# STM32H750VBT6_USB3300.net
KiCad netlist of a schematic drawn in EasyEDA Pro
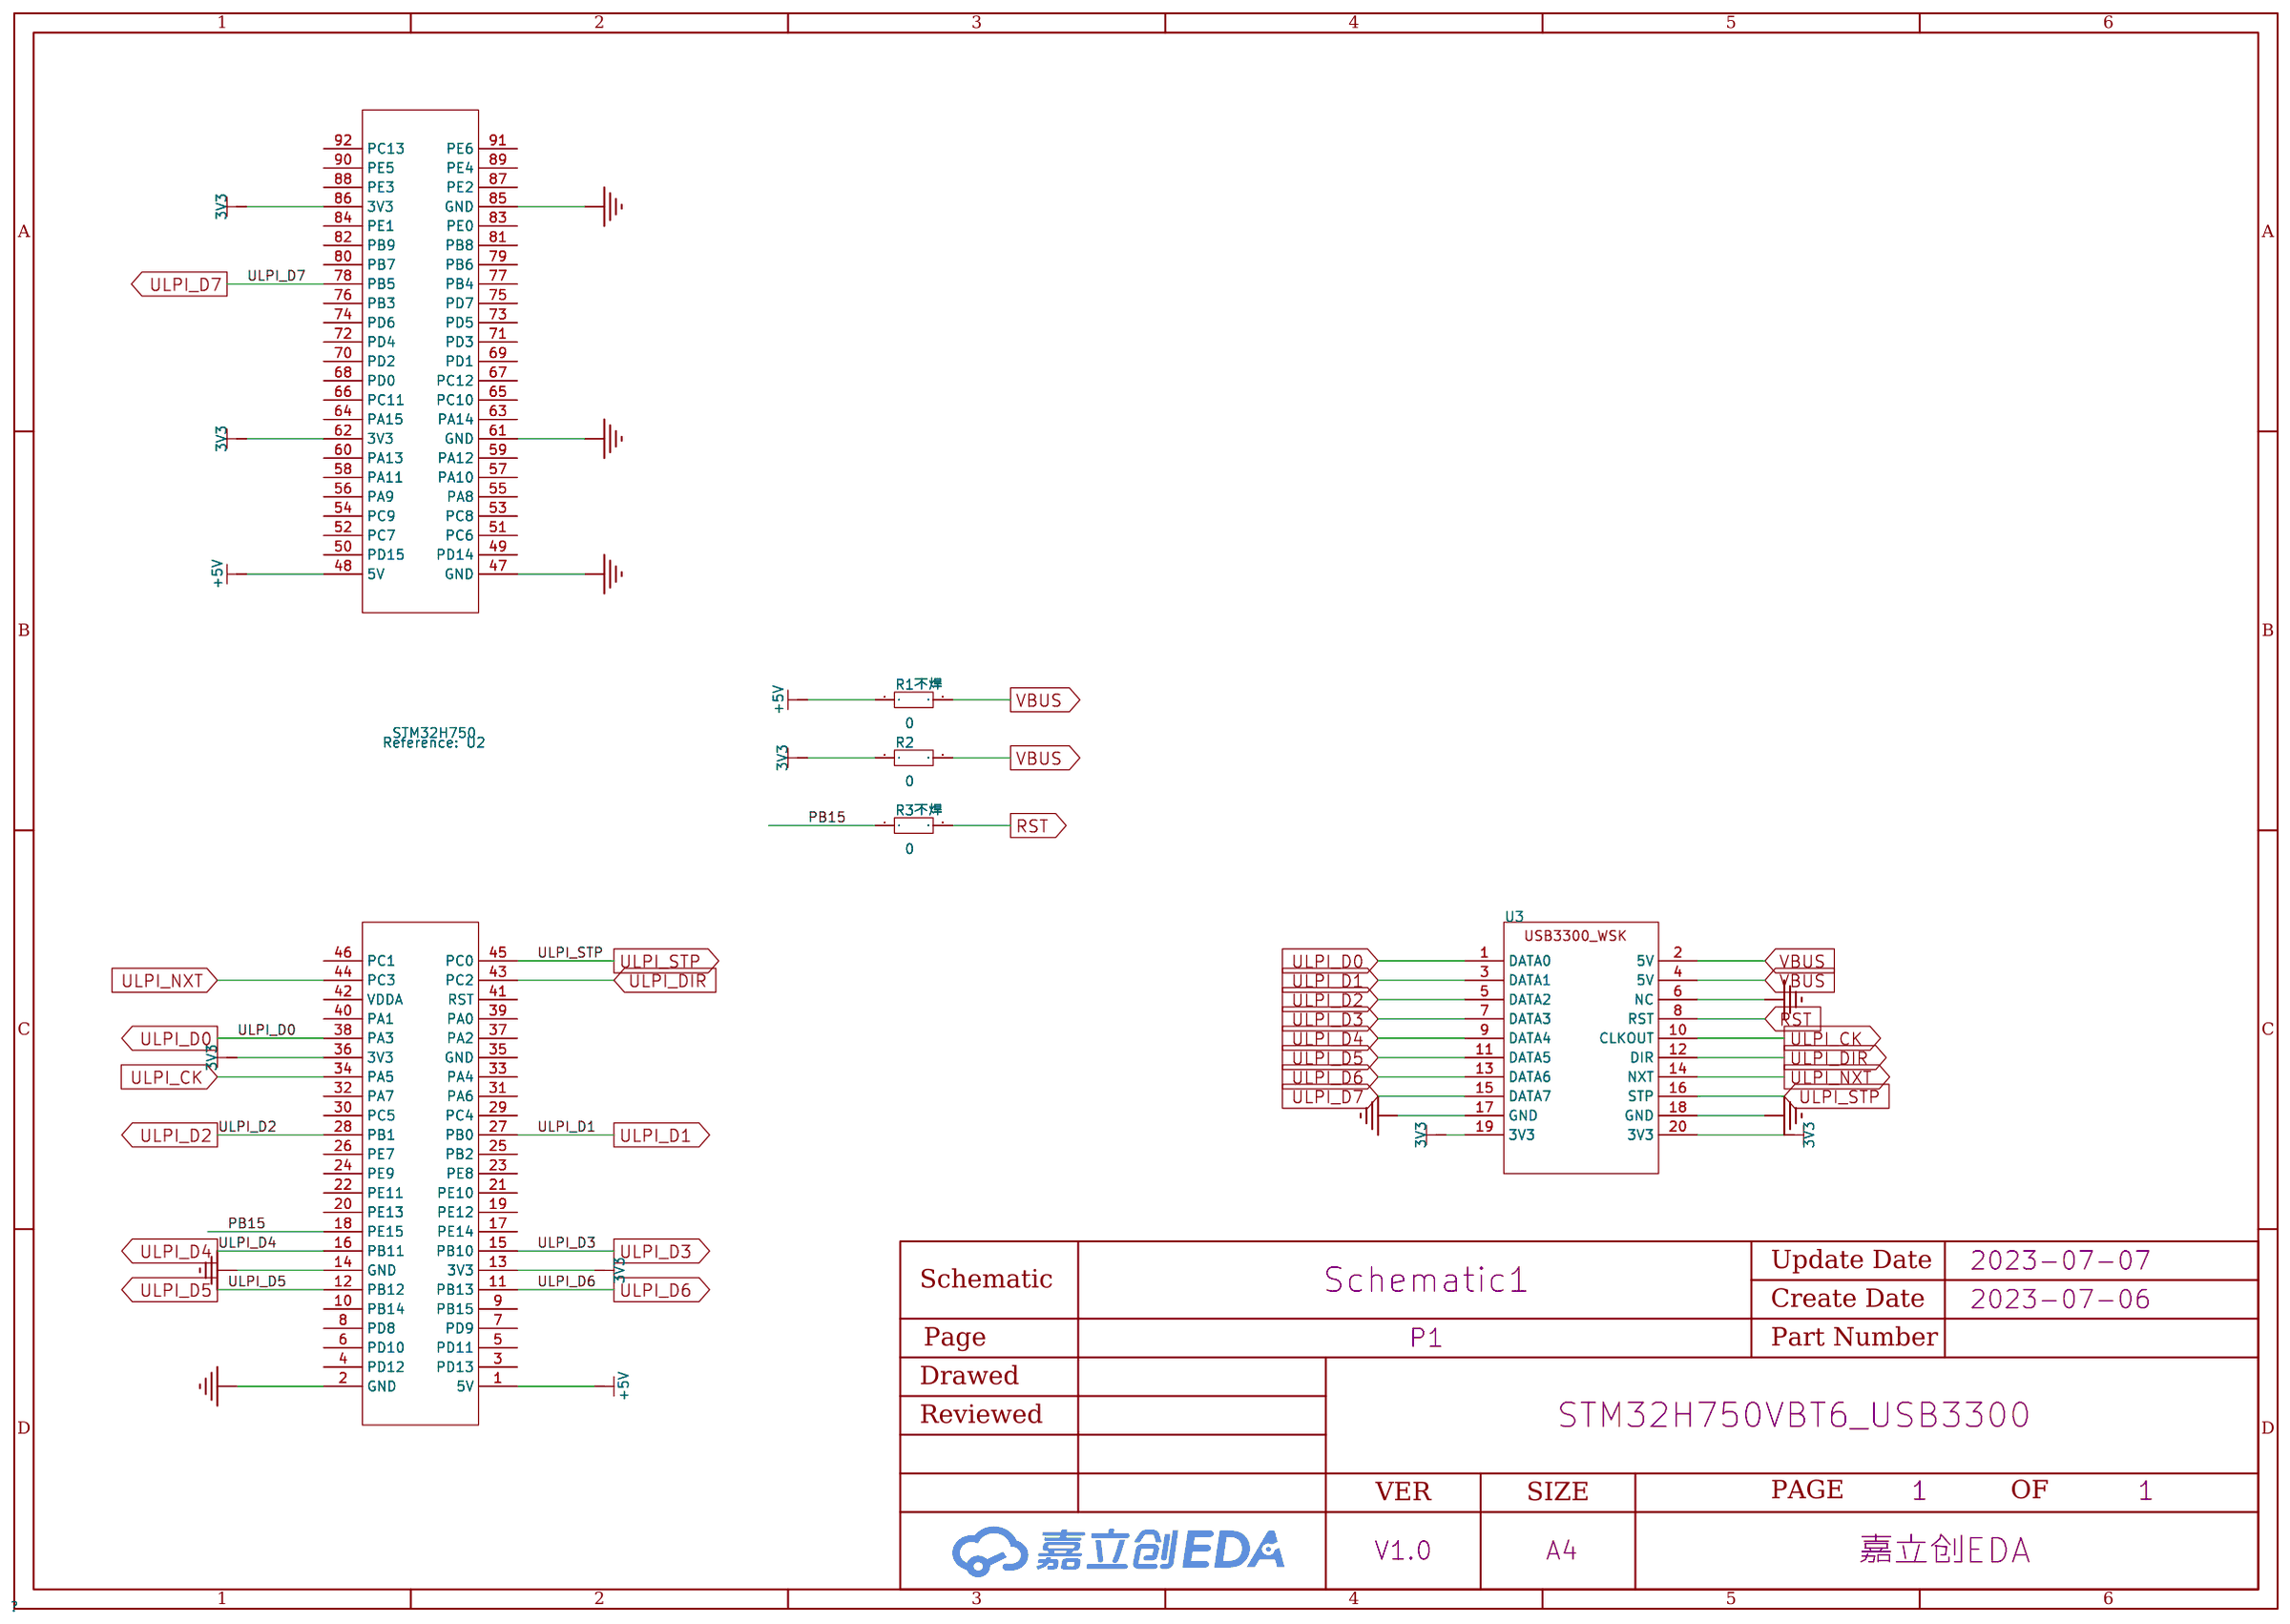
[diagram p0: schematic sheet]

(export (version "E")
  (design (tool "Eeschema 10.0.6"))
  (components
    (comp (ref "R1不焊") (value "0") (footprint "easyedapro:R0603") (libsource (lib "easyedapro") (part "电阻")))
    (comp (ref "R2") (value "0") (footprint "easyedapro:R0603") (libsource (lib "easyedapro") (part "电阻")))
    (comp (ref "R3不焊") (value "0") (footprint "easyedapro:R0603") (libsource (lib "easyedapro") (part "电阻")))
    (comp (ref "U2")
      (value "STM32H750")
      (description "STM32H750VBT6核心板")
      (libsource (lib "easyedapro") (part "STM32H750VBT6"))
    )
    (comp (ref "U3")
      (value "~")
      (description "微雪USB3300 ULPI接口模块")
      (libsource (lib "easyedapro") (part "USB3300_wireshark"))
    )
  )
  (nets
    (net (code "1") (name "+5V") (class "Default")
      (node (ref "R1不焊") (pin "1") (pinfunction "1_1") (pintype "input"))
      (node (ref "U2") (pin "1") (pinfunction "5V_1") (pintype "input"))
      (node (ref "U2") (pin "48") (pinfunction "5V_48") (pintype "input"))
    )
    (net (code "2") (name "/PB15") (class "Default")
      (node (ref "R3不焊") (pin "1") (pinfunction "1_1") (pintype "input"))
      (node (ref "U2") (pin "18") (pinfunction "PE15_18") (pintype "input"))
    )
    (net (code "3") (name "3V3") (class "Default")
      (node (ref "R2") (pin "1") (pinfunction "1_1") (pintype "input"))
      (node (ref "U2") (pin "13") (pinfunction "3V3_13") (pintype "input"))
      (node (ref "U2") (pin "36") (pinfunction "3V3_36") (pintype "input"))
      (node (ref "U2") (pin "62") (pinfunction "3V3_62") (pintype "input"))
      (node (ref "U2") (pin "86") (pinfunction "3V3_86") (pintype "input"))
      (node (ref "U3") (pin "19") (pinfunction "3V3_19") (pintype "input"))
      (node (ref "U3") (pin "20") (pinfunction "3V3_20") (pintype "input"))
    )
    (net (code "4") (name "GND") (class "Default")
      (node (ref "U2") (pin "14") (pinfunction "GND_14") (pintype "input"))
      (node (ref "U2") (pin "2") (pinfunction "GND_2") (pintype "input"))
      (node (ref "U2") (pin "47") (pinfunction "GND_47") (pintype "input"))
      (node (ref "U2") (pin "61") (pinfunction "GND_61") (pintype "input"))
      (node (ref "U2") (pin "85") (pinfunction "GND_85") (pintype "input"))
      (node (ref "U3") (pin "17") (pinfunction "GND_17") (pintype "input"))
      (node (ref "U3") (pin "18") (pinfunction "GND_18") (pintype "input"))
      (node (ref "U3") (pin "6") (pinfunction "NC_6") (pintype "input"))
    )
    (net (code "5") (name "RST") (class "Default")
      (node (ref "R3不焊") (pin "2") (pinfunction "2_2") (pintype "input"))
      (node (ref "U3") (pin "8") (pinfunction "RST_8") (pintype "input"))
    )
    (net (code "6") (name "ULPI_CK") (class "Default")
      (node (ref "U2") (pin "34") (pinfunction "PA5_34") (pintype "input"))
      (node (ref "U3") (pin "10") (pinfunction "CLKOUT_10") (pintype "input"))
    )
    (net (code "7") (name "ULPI_D0") (class "Default")
      (node (ref "U2") (pin "38") (pinfunction "PA3_38") (pintype "input"))
      (node (ref "U3") (pin "1") (pinfunction "DATA0_1") (pintype "input"))
    )
    (net (code "8") (name "ULPI_D1") (class "Default")
      (node (ref "U2") (pin "27") (pinfunction "PB0_27") (pintype "input"))
      (node (ref "U3") (pin "3") (pinfunction "DATA1_3") (pintype "input"))
    )
    (net (code "9") (name "ULPI_D2") (class "Default")
      (node (ref "U2") (pin "28") (pinfunction "PB1_28") (pintype "input"))
      (node (ref "U3") (pin "5") (pinfunction "DATA2_5") (pintype "input"))
    )
    (net (code "10") (name "ULPI_D3") (class "Default")
      (node (ref "U2") (pin "15") (pinfunction "PB10_15") (pintype "input"))
      (node (ref "U3") (pin "7") (pinfunction "DATA3_7") (pintype "input"))
    )
    (net (code "11") (name "ULPI_D4") (class "Default")
      (node (ref "U2") (pin "16") (pinfunction "PB11_16") (pintype "input"))
      (node (ref "U3") (pin "9") (pinfunction "DATA4_9") (pintype "input"))
    )
    (net (code "12") (name "ULPI_D5") (class "Default")
      (node (ref "U2") (pin "12") (pinfunction "PB12_12") (pintype "input"))
      (node (ref "U3") (pin "11") (pinfunction "DATA5_11") (pintype "input"))
    )
    (net (code "13") (name "ULPI_D6") (class "Default")
      (node (ref "U2") (pin "11") (pinfunction "PB13_11") (pintype "input"))
      (node (ref "U3") (pin "13") (pinfunction "DATA6_13") (pintype "input"))
    )
    (net (code "14") (name "ULPI_D7") (class "Default")
      (node (ref "U2") (pin "78") (pinfunction "PB5_78") (pintype "input"))
      (node (ref "U3") (pin "15") (pinfunction "DATA7_15") (pintype "input"))
    )
    (net (code "15") (name "ULPI_DIR") (class "Default")
      (node (ref "U2") (pin "43") (pinfunction "PC2_43") (pintype "input"))
      (node (ref "U3") (pin "12") (pinfunction "DIR_12") (pintype "input"))
    )
    (net (code "16") (name "ULPI_NXT") (class "Default")
      (node (ref "U2") (pin "44") (pinfunction "PC3_44") (pintype "input"))
      (node (ref "U3") (pin "14") (pinfunction "NXT_14") (pintype "input"))
    )
    (net (code "17") (name "ULPI_STP") (class "Default")
      (node (ref "U2") (pin "45") (pinfunction "PC0_45") (pintype "input"))
      (node (ref "U3") (pin "16") (pinfunction "STP_16") (pintype "input"))
    )
    (net (code "18") (name "VBUS") (class "Default")
      (node (ref "R1不焊") (pin "2") (pinfunction "2_2") (pintype "input"))
      (node (ref "R2") (pin "2") (pinfunction "2_2") (pintype "input"))
      (node (ref "U3") (pin "2") (pinfunction "5V_2") (pintype "input"))
      (node (ref "U3") (pin "4") (pinfunction "5V_4") (pintype "input"))
    )
    (net (code "19") (name "unconnected-(U2-GND-Pad35)") (class "Default")
      (node (ref "U2") (pin "35") (pinfunction "GND_35") (pintype "input"))
    )
    (net (code "20") (name "unconnected-(U2-PA0-Pad39)") (class "Default")
      (node (ref "U2") (pin "39") (pinfunction "PA0_39") (pintype "input"))
    )
    (net (code "21") (name "unconnected-(U2-PA1-Pad40)") (class "Default")
      (node (ref "U2") (pin "40") (pinfunction "PA1_40") (pintype "input"))
    )
    (net (code "22") (name "unconnected-(U2-PA2-Pad37)") (class "Default")
      (node (ref "U2") (pin "37") (pinfunction "PA2_37") (pintype "input"))
    )
    (net (code "23") (name "unconnected-(U2-PA4-Pad33)") (class "Default")
      (node (ref "U2") (pin "33") (pinfunction "PA4_33") (pintype "input"))
    )
    (net (code "24") (name "unconnected-(U2-PA6-Pad31)") (class "Default")
      (node (ref "U2") (pin "31") (pinfunction "PA6_31") (pintype "input"))
    )
    (net (code "25") (name "unconnected-(U2-PA7-Pad32)") (class "Default")
      (node (ref "U2") (pin "32") (pinfunction "PA7_32") (pintype "input"))
    )
    (net (code "26") (name "unconnected-(U2-PA8-Pad55)") (class "Default")
      (node (ref "U2") (pin "55") (pinfunction "PA8_55") (pintype "input"))
    )
    (net (code "27") (name "unconnected-(U2-PA9-Pad56)") (class "Default")
      (node (ref "U2") (pin "56") (pinfunction "PA9_56") (pintype "input"))
    )
    (net (code "28") (name "unconnected-(U2-PA10-Pad57)") (class "Default")
      (node (ref "U2") (pin "57") (pinfunction "PA10_57") (pintype "input"))
    )
    (net (code "29") (name "unconnected-(U2-PA11-Pad58)") (class "Default")
      (node (ref "U2") (pin "58") (pinfunction "PA11_58") (pintype "input"))
    )
    (net (code "30") (name "unconnected-(U2-PA12-Pad59)") (class "Default")
      (node (ref "U2") (pin "59") (pinfunction "PA12_59") (pintype "input"))
    )
    (net (code "31") (name "unconnected-(U2-PA13-Pad60)") (class "Default")
      (node (ref "U2") (pin "60") (pinfunction "PA13_60") (pintype "input"))
    )
    (net (code "32") (name "unconnected-(U2-PA14-Pad63)") (class "Default")
      (node (ref "U2") (pin "63") (pinfunction "PA14_63") (pintype "input"))
    )
    (net (code "33") (name "unconnected-(U2-PA15-Pad64)") (class "Default")
      (node (ref "U2") (pin "64") (pinfunction "PA15_64") (pintype "input"))
    )
    (net (code "34") (name "unconnected-(U2-PB2-Pad25)") (class "Default")
      (node (ref "U2") (pin "25") (pinfunction "PB2_25") (pintype "input"))
    )
    (net (code "35") (name "unconnected-(U2-PB3-Pad76)") (class "Default")
      (node (ref "U2") (pin "76") (pinfunction "PB3_76") (pintype "input"))
    )
    (net (code "36") (name "unconnected-(U2-PB4-Pad77)") (class "Default")
      (node (ref "U2") (pin "77") (pinfunction "PB4_77") (pintype "input"))
    )
    (net (code "37") (name "unconnected-(U2-PB6-Pad79)") (class "Default")
      (node (ref "U2") (pin "79") (pinfunction "PB6_79") (pintype "input"))
    )
    (net (code "38") (name "unconnected-(U2-PB7-Pad80)") (class "Default")
      (node (ref "U2") (pin "80") (pinfunction "PB7_80") (pintype "input"))
    )
    (net (code "39") (name "unconnected-(U2-PB8-Pad81)") (class "Default")
      (node (ref "U2") (pin "81") (pinfunction "PB8_81") (pintype "input"))
    )
    (net (code "40") (name "unconnected-(U2-PB9-Pad82)") (class "Default")
      (node (ref "U2") (pin "82") (pinfunction "PB9_82") (pintype "input"))
    )
    (net (code "41") (name "unconnected-(U2-PB14-Pad10)") (class "Default")
      (node (ref "U2") (pin "10") (pinfunction "PB14_10") (pintype "input"))
    )
    (net (code "42") (name "unconnected-(U2-PB15-Pad9)") (class "Default")
      (node (ref "U2") (pin "9") (pinfunction "PB15_9") (pintype "input"))
    )
    (net (code "43") (name "unconnected-(U2-PC1-Pad46)") (class "Default")
      (node (ref "U2") (pin "46") (pinfunction "PC1_46") (pintype "input"))
    )
    (net (code "44") (name "unconnected-(U2-PC4-Pad29)") (class "Default")
      (node (ref "U2") (pin "29") (pinfunction "PC4_29") (pintype "input"))
    )
    (net (code "45") (name "unconnected-(U2-PC5-Pad30)") (class "Default")
      (node (ref "U2") (pin "30") (pinfunction "PC5_30") (pintype "input"))
    )
    (net (code "46") (name "unconnected-(U2-PC6-Pad51)") (class "Default")
      (node (ref "U2") (pin "51") (pinfunction "PC6_51") (pintype "input"))
    )
    (net (code "47") (name "unconnected-(U2-PC7-Pad52)") (class "Default")
      (node (ref "U2") (pin "52") (pinfunction "PC7_52") (pintype "input"))
    )
    (net (code "48") (name "unconnected-(U2-PC8-Pad53)") (class "Default")
      (node (ref "U2") (pin "53") (pinfunction "PC8_53") (pintype "input"))
    )
    (net (code "49") (name "unconnected-(U2-PC9-Pad54)") (class "Default")
      (node (ref "U2") (pin "54") (pinfunction "PC9_54") (pintype "input"))
    )
    (net (code "50") (name "unconnected-(U2-PC10-Pad65)") (class "Default")
      (node (ref "U2") (pin "65") (pinfunction "PC10_65") (pintype "input"))
    )
    (net (code "51") (name "unconnected-(U2-PC11-Pad66)") (class "Default")
      (node (ref "U2") (pin "66") (pinfunction "PC11_66") (pintype "input"))
    )
    (net (code "52") (name "unconnected-(U2-PC12-Pad67)") (class "Default")
      (node (ref "U2") (pin "67") (pinfunction "PC12_67") (pintype "input"))
    )
    (net (code "53") (name "unconnected-(U2-PC13-Pad92)") (class "Default")
      (node (ref "U2") (pin "92") (pinfunction "PC13_92") (pintype "input"))
    )
    (net (code "54") (name "unconnected-(U2-PD0-Pad68)") (class "Default")
      (node (ref "U2") (pin "68") (pinfunction "PD0_68") (pintype "input"))
    )
    (net (code "55") (name "unconnected-(U2-PD1-Pad69)") (class "Default")
      (node (ref "U2") (pin "69") (pinfunction "PD1_69") (pintype "input"))
    )
    (net (code "56") (name "unconnected-(U2-PD2-Pad70)") (class "Default")
      (node (ref "U2") (pin "70") (pinfunction "PD2_70") (pintype "input"))
    )
    (net (code "57") (name "unconnected-(U2-PD3-Pad71)") (class "Default")
      (node (ref "U2") (pin "71") (pinfunction "PD3_71") (pintype "input"))
    )
    (net (code "58") (name "unconnected-(U2-PD4-Pad72)") (class "Default")
      (node (ref "U2") (pin "72") (pinfunction "PD4_72") (pintype "input"))
    )
    (net (code "59") (name "unconnected-(U2-PD5-Pad73)") (class "Default")
      (node (ref "U2") (pin "73") (pinfunction "PD5_73") (pintype "input"))
    )
    (net (code "60") (name "unconnected-(U2-PD6-Pad74)") (class "Default")
      (node (ref "U2") (pin "74") (pinfunction "PD6_74") (pintype "input"))
    )
    (net (code "61") (name "unconnected-(U2-PD7-Pad75)") (class "Default")
      (node (ref "U2") (pin "75") (pinfunction "PD7_75") (pintype "input"))
    )
    (net (code "62") (name "unconnected-(U2-PD8-Pad8)") (class "Default")
      (node (ref "U2") (pin "8") (pinfunction "PD8_8") (pintype "input"))
    )
    (net (code "63") (name "unconnected-(U2-PD9-Pad7)") (class "Default")
      (node (ref "U2") (pin "7") (pinfunction "PD9_7") (pintype "input"))
    )
    (net (code "64") (name "unconnected-(U2-PD10-Pad6)") (class "Default")
      (node (ref "U2") (pin "6") (pinfunction "PD10_6") (pintype "input"))
    )
    (net (code "65") (name "unconnected-(U2-PD11-Pad5)") (class "Default")
      (node (ref "U2") (pin "5") (pinfunction "PD11_5") (pintype "input"))
    )
    (net (code "66") (name "unconnected-(U2-PD12-Pad4)") (class "Default")
      (node (ref "U2") (pin "4") (pinfunction "PD12_4") (pintype "input"))
    )
    (net (code "67") (name "unconnected-(U2-PD13-Pad3)") (class "Default")
      (node (ref "U2") (pin "3") (pinfunction "PD13_3") (pintype "input"))
    )
    (net (code "68") (name "unconnected-(U2-PD14-Pad49)") (class "Default")
      (node (ref "U2") (pin "49") (pinfunction "PD14_49") (pintype "input"))
    )
    (net (code "69") (name "unconnected-(U2-PD15-Pad50)") (class "Default")
      (node (ref "U2") (pin "50") (pinfunction "PD15_50") (pintype "input"))
    )
    (net (code "70") (name "unconnected-(U2-PE0-Pad83)") (class "Default")
      (node (ref "U2") (pin "83") (pinfunction "PE0_83") (pintype "input"))
    )
    (net (code "71") (name "unconnected-(U2-PE1-Pad84)") (class "Default")
      (node (ref "U2") (pin "84") (pinfunction "PE1_84") (pintype "input"))
    )
    (net (code "72") (name "unconnected-(U2-PE2-Pad87)") (class "Default")
      (node (ref "U2") (pin "87") (pinfunction "PE2_87") (pintype "input"))
    )
    (net (code "73") (name "unconnected-(U2-PE3-Pad88)") (class "Default")
      (node (ref "U2") (pin "88") (pinfunction "PE3_88") (pintype "input"))
    )
    (net (code "74") (name "unconnected-(U2-PE4-Pad89)") (class "Default")
      (node (ref "U2") (pin "89") (pinfunction "PE4_89") (pintype "input"))
    )
    (net (code "75") (name "unconnected-(U2-PE5-Pad90)") (class "Default")
      (node (ref "U2") (pin "90") (pinfunction "PE5_90") (pintype "input"))
    )
    (net (code "76") (name "unconnected-(U2-PE6-Pad91)") (class "Default")
      (node (ref "U2") (pin "91") (pinfunction "PE6_91") (pintype "input"))
    )
    (net (code "77") (name "unconnected-(U2-PE7-Pad26)") (class "Default")
      (node (ref "U2") (pin "26") (pinfunction "PE7_26") (pintype "input"))
    )
    (net (code "78") (name "unconnected-(U2-PE8-Pad23)") (class "Default")
      (node (ref "U2") (pin "23") (pinfunction "PE8_23") (pintype "input"))
    )
    (net (code "79") (name "unconnected-(U2-PE9-Pad24)") (class "Default")
      (node (ref "U2") (pin "24") (pinfunction "PE9_24") (pintype "input"))
    )
    (net (code "80") (name "unconnected-(U2-PE10-Pad21)") (class "Default")
      (node (ref "U2") (pin "21") (pinfunction "PE10_21") (pintype "input"))
    )
    (net (code "81") (name "unconnected-(U2-PE11-Pad22)") (class "Default")
      (node (ref "U2") (pin "22") (pinfunction "PE11_22") (pintype "input"))
    )
    (net (code "82") (name "unconnected-(U2-PE12-Pad19)") (class "Default")
      (node (ref "U2") (pin "19") (pinfunction "PE12_19") (pintype "input"))
    )
    (net (code "83") (name "unconnected-(U2-PE13-Pad20)") (class "Default")
      (node (ref "U2") (pin "20") (pinfunction "PE13_20") (pintype "input"))
    )
    (net (code "84") (name "unconnected-(U2-PE14-Pad17)") (class "Default")
      (node (ref "U2") (pin "17") (pinfunction "PE14_17") (pintype "input"))
    )
    (net (code "85") (name "unconnected-(U2-RST-Pad41)") (class "Default")
      (node (ref "U2") (pin "41") (pinfunction "RST_41") (pintype "input"))
    )
    (net (code "86") (name "unconnected-(U2-VDDA-Pad42)") (class "Default")
      (node (ref "U2") (pin "42") (pinfunction "VDDA_42") (pintype "input"))
    )
  )
)
